# oledm204.net
KiCad netlist of a schematic drawn in EAGLE
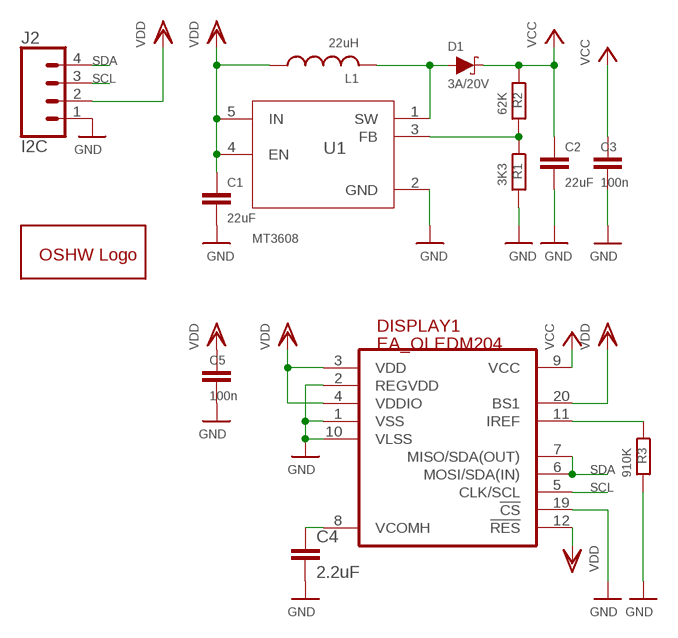
[diagram p0: schematic, sheet 1]

(export (version "E")
  (design (tool "Eeschema 10.0.6"))
  (components
    (comp (ref "C1")
      (value "22uF")
      (footprint "eagle-import:C0603")
      (libsource (lib "eagle-import") (part "C-EUC0603"))
    )
    (comp (ref "C2")
      (value "22uF")
      (footprint "eagle-import:C0603")
      (libsource (lib "eagle-import") (part "C-EUC0603"))
    )
    (comp (ref "C3")
      (value "100n")
      (footprint "eagle-import:C0603")
      (libsource (lib "eagle-import") (part "C-EUC0603"))
    )
    (comp (ref "C4")
      (value "2.2uF")
      (footprint "eagle-import:C0603")
      (libsource (lib "eagle-import") (part "C-EUC0603"))
    )
    (comp (ref "C5")
      (value "100n")
      (footprint "eagle-import:C0603")
      (libsource (lib "eagle-import") (part "C-EUC0603"))
    )
    (comp (ref "D1")
      (value "3A/20V")
      (footprint "eagle-import:SMA-DIODE")
      (libsource (lib "eagle-import") (part "DIODE-SCHOTTKY-SS14"))
    )
    (comp (ref "DISPLAY1")
      (value "EA_OLEDM204")
      (footprint "eagle-import:EA_OLEDM204")
      (libsource (lib "eagle-import") (part "EA_OLEDM204"))
    )
    (comp (ref "GOLD_ORB_SM1")
      (value "OSHWLOGOLOGO5MM")
      (footprint "eagle-import:OSHW_5MM")
      (libsource (lib "eagle-import") (part "OSHWLOGOLOGO5MM"))
    )
    (comp (ref "J2")
      (value "I2C")
      (footprint "eagle-import:1X04")
      (libsource (lib "eagle-import") (part "CONN_04"))
    )
    (comp (ref "L1")
      (value "22uH")
      (footprint "eagle-import:PIS2816")
      (libsource (lib "eagle-import") (part "L-USPIS2816"))
    )
    (comp (ref "R1")
      (value "3K3")
      (footprint "eagle-import:R0402")
      (libsource (lib "eagle-import") (part "R-EU_R0402"))
    )
    (comp (ref "R2")
      (value "62K")
      (footprint "eagle-import:R0402")
      (libsource (lib "eagle-import") (part "R-EU_R0402"))
    )
    (comp (ref "R3")
      (value "910K")
      (footprint "eagle-import:R0402")
      (libsource (lib "eagle-import") (part "R-EU_R0402"))
    )
    (comp (ref "U1")
      (value "MT3608")
      (footprint "eagle-import:SOT95P280X145-6N")
      (fields (field (name "MF") "Aerosemi Technology Co., Ltd"))
      (libsource (lib "eagle-import") (part "MT3608"))
    )
  )
  (nets
    (net (code "1") (name "/SCL") (class "Default")
      (node (ref "DISPLAY1") (pin "5") (pinfunction "CLK/SCL_5") (pintype "input"))
      (node (ref "J2") (pin "3") (pinfunction "3_3") (pintype "passive"))
    )
    (net (code "2") (name "/SDA") (class "Default")
      (node (ref "DISPLAY1") (pin "6") (pinfunction "MOSI/SDA(IN)_6") (pintype "input"))
      (node (ref "DISPLAY1") (pin "7") (pinfunction "MISO/SDA(OUT)_7") (pintype "output"))
      (node (ref "J2") (pin "4") (pinfunction "4_4") (pintype "passive"))
    )
    (net (code "3") (name "GND") (class "Default")
      (node (ref "C1") (pin "2") (pinfunction "2_2") (pintype "passive"))
      (node (ref "C2") (pin "2") (pinfunction "2_2") (pintype "passive"))
      (node (ref "C3") (pin "2") (pinfunction "2_2") (pintype "passive"))
      (node (ref "C4") (pin "2") (pinfunction "2_2") (pintype "passive"))
      (node (ref "C5") (pin "2") (pinfunction "2_2") (pintype "passive"))
      (node (ref "DISPLAY1") (pin "1") (pinfunction "VSS_1") (pintype "power_in"))
      (node (ref "DISPLAY1") (pin "10") (pinfunction "VLSS_10") (pintype "power_in"))
      (node (ref "DISPLAY1") (pin "19") (pinfunction "~{CS}_19") (pintype "input"))
      (node (ref "DISPLAY1") (pin "2") (pinfunction "REGVDD_2") (pintype "power_in"))
      (node (ref "J2") (pin "1") (pinfunction "1_1") (pintype "passive"))
      (node (ref "R1") (pin "2") (pinfunction "2_2") (pintype "passive"))
      (node (ref "R3") (pin "2") (pinfunction "2_2") (pintype "passive"))
      (node (ref "U1") (pin "2") (pinfunction "GND_2") (pintype "power_in"))
    )
    (net (code "4") (name "Net-(DISPLAY1-IREF)") (class "Default")
      (node (ref "DISPLAY1") (pin "11") (pinfunction "IREF_11") (pintype "passive"))
      (node (ref "R3") (pin "1") (pinfunction "1_1") (pintype "passive"))
    )
    (net (code "5") (name "Net-(DISPLAY1-VCOMH)") (class "Default")
      (node (ref "C4") (pin "1") (pinfunction "1_1") (pintype "passive"))
      (node (ref "DISPLAY1") (pin "8") (pinfunction "VCOMH_8") (pintype "passive"))
    )
    (net (code "6") (name "Net-(U1-FB)") (class "Default")
      (node (ref "R1") (pin "1") (pinfunction "1_1") (pintype "passive"))
      (node (ref "R2") (pin "2") (pinfunction "2_2") (pintype "passive"))
      (node (ref "U1") (pin "3") (pinfunction "FB_3") (pintype "input"))
    )
    (net (code "7") (name "Net-(U1-SW)") (class "Default")
      (node (ref "D1") (pin "A") (pinfunction "A_A") (pintype "passive"))
      (node (ref "L1") (pin "2") (pinfunction "2_2") (pintype "passive"))
      (node (ref "U1") (pin "1") (pinfunction "SW_1") (pintype "output"))
    )
    (net (code "8") (name "VCC") (class "Default")
      (node (ref "C2") (pin "1") (pinfunction "1_1") (pintype "passive"))
      (node (ref "C3") (pin "1") (pinfunction "1_1") (pintype "passive"))
      (node (ref "D1") (pin "C") (pinfunction "C_C") (pintype "passive"))
      (node (ref "DISPLAY1") (pin "9") (pinfunction "VCC_9") (pintype "power_in"))
      (node (ref "R2") (pin "1") (pinfunction "1_1") (pintype "passive"))
    )
    (net (code "9") (name "VDD") (class "Default")
      (node (ref "C1") (pin "1") (pinfunction "1_1") (pintype "passive"))
      (node (ref "C5") (pin "1") (pinfunction "1_1") (pintype "passive"))
      (node (ref "DISPLAY1") (pin "12") (pinfunction "~{RES}_12") (pintype "input"))
      (node (ref "DISPLAY1") (pin "20") (pinfunction "BS1_20") (pintype "input"))
      (node (ref "DISPLAY1") (pin "3") (pinfunction "VDD_3") (pintype "power_in"))
      (node (ref "DISPLAY1") (pin "4") (pinfunction "VDDIO_4") (pintype "power_in"))
      (node (ref "J2") (pin "2") (pinfunction "2_2") (pintype "passive"))
      (node (ref "L1") (pin "1") (pinfunction "1_1") (pintype "passive"))
      (node (ref "U1") (pin "4") (pinfunction "EN_4") (pintype "input"))
      (node (ref "U1") (pin "5") (pinfunction "IN_5") (pintype "input"))
    )
  )
)
